# 04_-_COMMUNICATION.net
KiCad netlist of a schematic drawn in Altium Designer
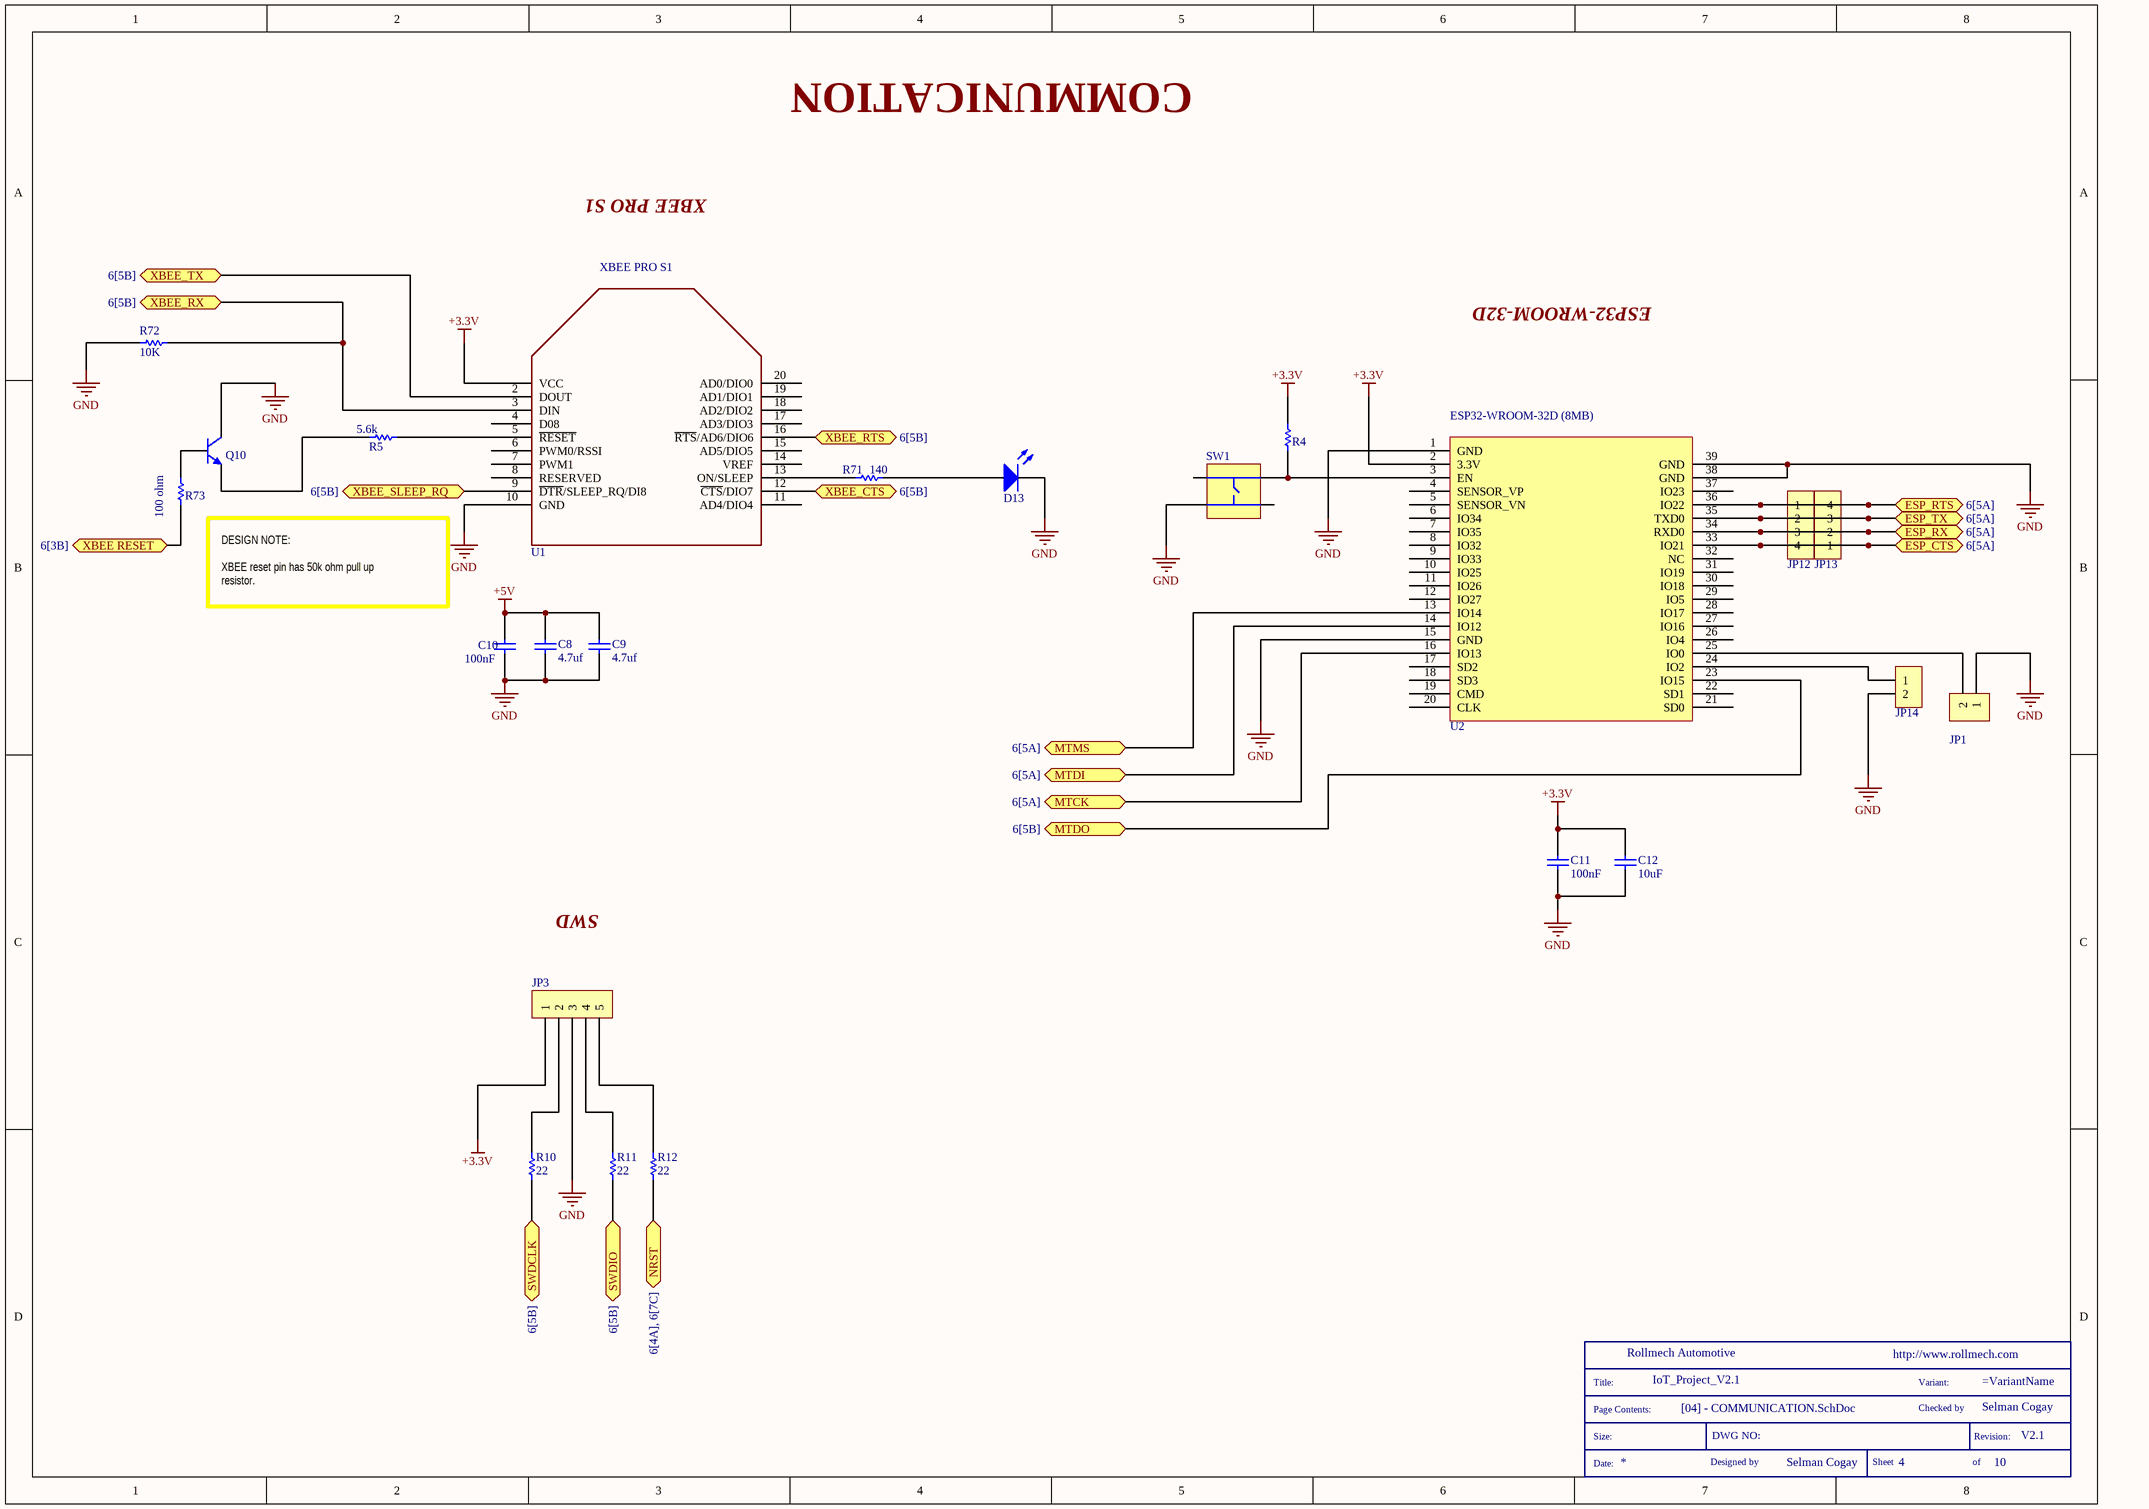
[diagram p0: [04] - COMMUNICATION.SchDoc]

(export (version "E")
  (design (tool "Eeschema 10.0.6"))
  (components
    (comp (ref "C8")
      (value "4.7uf")
      (footprint "CAP_CER_0603")
      (description "CAP CER 4.7PF 50V C0G 0603")
      (libsource (lib "Rollmech_Altium") (part "CGA3E2C0G1H4R7C080AA"))
    )
    (comp (ref "C9")
      (value "4.7uf")
      (footprint "CAP_CER_0603")
      (description "CAP CER 4.7PF 50V C0G 0603")
      (libsource (lib "Rollmech_Altium") (part "CGA3E2C0G1H4R7C080AA"))
    )
    (comp (ref "C10")
      (value "100nF")
      (footprint "CAP_CER_0603")
      (description "CAP CER 100nf 35V X5R 0603")
      (libsource (lib "Rollmech_Altium") (part "GMK107BJ104KAHT"))
    )
    (comp (ref "C11")
      (value "100nF")
      (footprint "CAP_CER_0603")
      (description "CAP CER 100nf 35V X5R 0603")
      (libsource (lib "Rollmech_Altium") (part "GMK107BJ104KAHT"))
    )
    (comp (ref "C12")
      (value "10uF")
      (footprint "CAP_CER_0805")
      (description "CAP CER 10UF 16V")
      (libsource (lib "Rollmech_Altium") (part "CGA4J1X5R1C106M125AC"))
    )
    (comp (ref "D13")
      (value "Blue Led")
      (footprint "RES_0603")
      (description "LED BLUE CLEAR 2SMD")
      (libsource (lib "Rollmech_Altium") (part "EAST16084BA8"))
    )
    (comp (ref "JP1")
      (value "HDR 1X2 2.54MM")
      (footprint "HDR_FEMALE_1X2_2.54MM")
      (description "HDR FEMALE 1X2 2.54MM")
      (libsource (lib "") (part "PPTC021LFBN-RC_1"))
    )
    (comp (ref "JP3")
      (value "HDR FEMALE 1X5 2.54MM")
      (footprint "HDR_FEMALE_1X5_2.54MM")
      (libsource (lib "Rollmech_Altium") (part "PPTC051LFBN-RC"))
    )
    (comp (ref "JP12")
      (value "HDR FEMALE 1X4 2.54MM")
      (footprint "HDR_FEMALE_1X4_2.54MM")
      (libsource (lib "") (part "PPTC041LFBN-RC_1"))
    )
    (comp (ref "JP13")
      (value "HDR FEMALE 1X4 2.54MM")
      (footprint "HDR_FEMALE_1X4_2.54MM")
      (libsource (lib "Rollmech_Altium") (part "PPTC041LFBN-RC"))
    )
    (comp (ref "JP14")
      (value "HDR 1X2 2.54MM")
      (footprint "HDR_FEMALE_1X2_2.54MM")
      (description "HDR FEMALE 1X2 2.54MM")
      (libsource (lib "Rollmech_Altium") (part "PPTC021LFBN-RC"))
    )
    (comp (ref "Q10")
      (value "NPN 0.6A")
      (footprint "SOT-23 (TO-236)")
      (description "TRANS NPN 40V 0.6A SMD SOT23-3")
      (libsource (lib "Rollmech_Altium") (part "MMBT2222A-7-F"))
    )
    (comp (ref "R4")
      (value "1K 1/8W")
      (footprint "RES_0805")
      (description "RES SMD 1K OHM")
      (libsource (lib "Rollmech_Altium") (part "ERJ-6ENF1001V"))
    )
    (comp (ref "R5")
      (value "5.6k")
      (footprint "RES_0805")
      (description "RES SMD 5.6K OHM 1% 1/8W 0805")
      (libsource (lib "Rollmech_Altium") (part "ERJ-6ENF5601V"))
    )
    (comp (ref "R10")
      (value "22")
      (footprint "RES_0805")
      (description "RES SMD 22 OHM 5% 1/8W 0805")
      (libsource (lib "Rollmech_Altium") (part "ERJ-6GEYJ220V"))
    )
    (comp (ref "R11")
      (value "22")
      (footprint "RES_0805")
      (description "RES SMD 22 OHM 5% 1/8W 0805")
      (libsource (lib "Rollmech_Altium") (part "ERJ-6GEYJ220V"))
    )
    (comp (ref "R12")
      (value "22")
      (footprint "RES_0805")
      (description "RES SMD 22 OHM 5% 1/8W 0805")
      (libsource (lib "Rollmech_Altium") (part "ERJ-6GEYJ220V"))
    )
    (comp (ref "R71")
      (value "140")
      (footprint "RES_0805")
      (description "RES SMD 140 OHM 1% 1/8W 0805")
      (libsource (lib "Rollmech_Altium") (part "ERJ-6ENF1400V"))
    )
    (comp (ref "R72")
      (value "10K")
      (footprint "RES_0805")
      (description "RES SMD 10K OHM 1% 1/8W 0805")
      (libsource (lib "Rollmech_Altium") (part "ERJ-6ENF1002V"))
    )
    (comp (ref "R73")
      (value "100 ohm")
      (footprint "RES_0805")
      (description "RES SMD 100 OHM")
      (libsource (lib "Rollmech_Altium") (part "ERJ-6ENF1000V"))
    )
    (comp (ref "SW1")
      (value "PTS 647 SK38 SMTR2 LFS")
      (footprint "4.5x4.5 Tactile switch")
      (description "SWITCH TACTILE 4.5 X 4.5")
      (libsource (lib "Rollmech_Altium") (part "PTS 647 SK38 SMTR2 LFS"))
    )
    (comp (ref "U1")
      (value "XBEE PRO S1")
      (footprint "XBEE PRO S1")
      (description "XBEE PRO SERIES1")
      (libsource (lib "Rollmech_Altium") (part "XBP24-DKSJ"))
    )
    (comp (ref "U2")
      (value "ESP32-WROOM-32D (8MB)")
      (footprint "ESP32-WROOM-32D")
      (description "ESP32 WIFI MODULE 64MBITS SPI FLASH")
      (libsource (lib "Rollmech_Altium") (part "ESP32-WROOM-32D (8MB)"))
    )
  )
  (nets
    (net (code "1") (name "+3.3V") (class "Default")
      (node (ref "C11") (pin "2") (pinfunction "2_2") (pintype "passive"))
      (node (ref "C12") (pin "2") (pinfunction "2_2") (pintype "passive"))
      (node (ref "JP3") (pin "1") (pinfunction "1_1") (pintype "passive"))
      (node (ref "R4") (pin "2") (pinfunction "2_2") (pintype "passive"))
      (node (ref "U1") (pin "1") (pinfunction "VCC_1") (pintype "passive"))
      (node (ref "U2") (pin "2") (pinfunction "3.3V_2") (pintype "passive"))
    )
    (net (code "2") (name "+5V") (class "Default")
      (node (ref "C10") (pin "2") (pinfunction "2_2") (pintype "passive"))
      (node (ref "C8") (pin "2") (pinfunction "2_2") (pintype "passive"))
      (node (ref "C9") (pin "2") (pinfunction "2_2") (pintype "passive"))
    )
    (net (code "3") (name "/ESP_CTS") (class "Default")
      (node (ref "JP12") (pin "4") (pinfunction "4_4") (pintype "passive"))
      (node (ref "JP13") (pin "1") (pinfunction "1_1") (pintype "passive"))
      (node (ref "U2") (pin "33") (pinfunction "IO21_33") (pintype "passive"))
    )
    (net (code "4") (name "/ESP_RTS") (class "Default")
      (node (ref "JP12") (pin "1") (pinfunction "1_1") (pintype "passive"))
      (node (ref "JP13") (pin "4") (pinfunction "4_4") (pintype "passive"))
      (node (ref "U2") (pin "36") (pinfunction "IO22_36") (pintype "passive"))
    )
    (net (code "5") (name "/ESP_RX") (class "Default")
      (node (ref "JP12") (pin "3") (pinfunction "3_3") (pintype "passive"))
      (node (ref "JP13") (pin "2") (pinfunction "2_2") (pintype "passive"))
      (node (ref "U2") (pin "34") (pinfunction "RXD0_34") (pintype "passive"))
    )
    (net (code "6") (name "/ESP_TX") (class "Default")
      (node (ref "JP12") (pin "2") (pinfunction "2_2") (pintype "passive"))
      (node (ref "JP13") (pin "3") (pinfunction "3_3") (pintype "passive"))
      (node (ref "U2") (pin "35") (pinfunction "TXD0_35") (pintype "passive"))
    )
    (net (code "7") (name "/MTCK") (class "Default")
      (node (ref "U2") (pin "16") (pinfunction "IO13_16") (pintype "passive"))
    )
    (net (code "8") (name "/MTDI") (class "Default")
      (node (ref "U2") (pin "14") (pinfunction "IO12_14") (pintype "passive"))
    )
    (net (code "9") (name "/MTDO") (class "Default")
      (node (ref "U2") (pin "23") (pinfunction "IO15_23") (pintype "passive"))
    )
    (net (code "10") (name "/MTMS") (class "Default")
      (node (ref "U2") (pin "13") (pinfunction "IO14_13") (pintype "passive"))
    )
    (net (code "11") (name "/NRST") (class "Default")
      (node (ref "R12") (pin "1") (pinfunction "1_1") (pintype "passive"))
    )
    (net (code "12") (name "/SWDCLK") (class "Default")
      (node (ref "R10") (pin "1") (pinfunction "1_1") (pintype "passive"))
    )
    (net (code "13") (name "/SWDIO") (class "Default")
      (node (ref "R11") (pin "1") (pinfunction "1_1") (pintype "passive"))
    )
    (net (code "14") (name "/XBEE RESET") (class "Default")
      (node (ref "R73") (pin "1") (pinfunction "1_1") (pintype "passive"))
    )
    (net (code "15") (name "/XBEE_CTS") (class "Default")
      (node (ref "U1") (pin "12") (pinfunction "~{CTS}/DIO7_12") (pintype "passive"))
    )
    (net (code "16") (name "/XBEE_RTS") (class "Default")
      (node (ref "U1") (pin "16") (pinfunction "~{RTS}/AD6/DIO6_16") (pintype "passive"))
    )
    (net (code "17") (name "/XBEE_RX") (class "Default")
      (node (ref "R72") (pin "2") (pinfunction "2_2") (pintype "passive"))
      (node (ref "U1") (pin "3") (pinfunction "DIN_3") (pintype "passive"))
    )
    (net (code "18") (name "/XBEE_SLEEP_RQ") (class "Default")
      (node (ref "U1") (pin "9") (pinfunction "~{DTR}/SLEEP_RQ/DI8_9") (pintype "passive"))
    )
    (net (code "19") (name "/XBEE_TX") (class "Default")
      (node (ref "U1") (pin "2") (pinfunction "DOUT_2") (pintype "passive"))
    )
    (net (code "20") (name "GND") (class "Default")
      (node (ref "C10") (pin "1") (pinfunction "1_1") (pintype "passive"))
      (node (ref "C11") (pin "1") (pinfunction "1_1") (pintype "passive"))
      (node (ref "C12") (pin "1") (pinfunction "1_1") (pintype "passive"))
      (node (ref "C8") (pin "1") (pinfunction "1_1") (pintype "passive"))
      (node (ref "C9") (pin "1") (pinfunction "1_1") (pintype "passive"))
      (node (ref "D13") (pin "2") (pinfunction "K_2") (pintype "passive"))
      (node (ref "JP1") (pin "1") (pinfunction "1_1") (pintype "passive"))
      (node (ref "JP14") (pin "2") (pinfunction "2_2") (pintype "passive"))
      (node (ref "JP3") (pin "3") (pinfunction "3_3") (pintype "passive"))
      (node (ref "Q10") (pin "1") (pinfunction "C_1") (pintype "passive"))
      (node (ref "R72") (pin "1") (pinfunction "1_1") (pintype "passive"))
      (node (ref "SW1") (pin "3") (pinfunction "3_3") (pintype "passive"))
      (node (ref "U1") (pin "10") (pinfunction "GND_10") (pintype "passive"))
      (node (ref "U2") (pin "1") (pinfunction "GND_1") (pintype "passive"))
      (node (ref "U2") (pin "15") (pinfunction "GND_15") (pintype "passive"))
      (node (ref "U2") (pin "38") (pinfunction "GND_38") (pintype "passive"))
      (node (ref "U2") (pin "39") (pinfunction "GND_39") (pintype "passive"))
    )
    (net (code "21") (name "Net-(D13-A)") (class "Default")
      (node (ref "D13") (pin "1") (pinfunction "A_1") (pintype "passive"))
      (node (ref "R71") (pin "2") (pinfunction "2_2") (pintype "passive"))
    )
    (net (code "22") (name "Net-(JP3-Pad2)") (class "Default")
      (node (ref "JP3") (pin "2") (pinfunction "2_2") (pintype "passive"))
      (node (ref "R10") (pin "2") (pinfunction "2_2") (pintype "passive"))
    )
    (net (code "23") (name "Net-(JP3-Pad4)") (class "Default")
      (node (ref "JP3") (pin "4") (pinfunction "4_4") (pintype "passive"))
      (node (ref "R11") (pin "2") (pinfunction "2_2") (pintype "passive"))
    )
    (net (code "24") (name "Net-(JP3-Pad5)") (class "Default")
      (node (ref "JP3") (pin "5") (pinfunction "5_5") (pintype "passive"))
      (node (ref "R12") (pin "2") (pinfunction "2_2") (pintype "passive"))
    )
    (net (code "25") (name "Net-(Q10-B)") (class "Default")
      (node (ref "Q10") (pin "2") (pinfunction "B_2") (pintype "passive"))
      (node (ref "R73") (pin "2") (pinfunction "2_2") (pintype "passive"))
    )
    (net (code "26") (name "Net-(Q10-E)") (class "Default")
      (node (ref "Q10") (pin "3") (pinfunction "E_3") (pintype "passive"))
      (node (ref "R5") (pin "2") (pinfunction "2_2") (pintype "passive"))
    )
    (net (code "27") (name "Net-(U1-ON{slash}SLEEP)") (class "Default")
      (node (ref "R71") (pin "1") (pinfunction "1_1") (pintype "passive"))
      (node (ref "U1") (pin "13") (pinfunction "ON/SLEEP_13") (pintype "passive"))
    )
    (net (code "28") (name "Net-(U1-~{RESET})") (class "Default")
      (node (ref "R5") (pin "1") (pinfunction "1_1") (pintype "passive"))
      (node (ref "U1") (pin "5") (pinfunction "~{RESET}_5") (pintype "passive"))
    )
    (net (code "29") (name "Net-(U2-EN)") (class "Default")
      (node (ref "R4") (pin "1") (pinfunction "1_1") (pintype "passive"))
      (node (ref "SW1") (pin "2") (pinfunction "2_2") (pintype "passive"))
      (node (ref "U2") (pin "3") (pinfunction "EN_3") (pintype "passive"))
    )
    (net (code "30") (name "Net-(U2-IO0)") (class "Default")
      (node (ref "JP1") (pin "2") (pinfunction "2_2") (pintype "passive"))
      (node (ref "U2") (pin "25") (pinfunction "IO0_25") (pintype "passive"))
    )
    (net (code "31") (name "Net-(U2-IO2)") (class "Default")
      (node (ref "JP14") (pin "1") (pinfunction "1_1") (pintype "passive"))
      (node (ref "U2") (pin "24") (pinfunction "IO2_24") (pintype "passive"))
    )
    (net (code "32") (name "unconnected-(SW1-Pad1)") (class "Default")
      (node (ref "SW1") (pin "1") (pinfunction "1_1") (pintype "passive"))
    )
    (net (code "33") (name "unconnected-(SW1-Pad4)") (class "Default")
      (node (ref "SW1") (pin "4") (pinfunction "4_4") (pintype "passive"))
    )
    (net (code "34") (name "unconnected-(U1-AD0{slash}DIO0-Pad20)") (class "Default")
      (node (ref "U1") (pin "20") (pinfunction "AD0/DIO0_20") (pintype "passive"))
    )
    (net (code "35") (name "unconnected-(U1-AD1{slash}DIO1-Pad19)") (class "Default")
      (node (ref "U1") (pin "19") (pinfunction "AD1/DIO1_19") (pintype "passive"))
    )
    (net (code "36") (name "unconnected-(U1-AD2{slash}DIO2-Pad18)") (class "Default")
      (node (ref "U1") (pin "18") (pinfunction "AD2/DIO2_18") (pintype "passive"))
    )
    (net (code "37") (name "unconnected-(U1-AD3{slash}DIO3-Pad17)") (class "Default")
      (node (ref "U1") (pin "17") (pinfunction "AD3/DIO3_17") (pintype "passive"))
    )
    (net (code "38") (name "unconnected-(U1-AD4{slash}DIO4-Pad11)") (class "Default")
      (node (ref "U1") (pin "11") (pinfunction "AD4/DIO4_11") (pintype "passive"))
    )
    (net (code "39") (name "unconnected-(U1-AD5{slash}DIO5-Pad15)") (class "Default")
      (node (ref "U1") (pin "15") (pinfunction "AD5/DIO5_15") (pintype "passive"))
    )
    (net (code "40") (name "unconnected-(U1-D08-Pad4)") (class "Default")
      (node (ref "U1") (pin "4") (pinfunction "D08_4") (pintype "passive"))
    )
    (net (code "41") (name "unconnected-(U1-PWM0{slash}RSSI-Pad6)") (class "Default")
      (node (ref "U1") (pin "6") (pinfunction "PWM0/RSSI_6") (pintype "passive"))
    )
    (net (code "42") (name "unconnected-(U1-PWM1-Pad7)") (class "Default")
      (node (ref "U1") (pin "7") (pinfunction "PWM1_7") (pintype "passive"))
    )
    (net (code "43") (name "unconnected-(U1-RESERVED-Pad8)") (class "Default")
      (node (ref "U1") (pin "8") (pinfunction "RESERVED_8") (pintype "passive"))
    )
    (net (code "44") (name "unconnected-(U1-VREF-Pad14)") (class "Default")
      (node (ref "U1") (pin "14") (pinfunction "VREF_14") (pintype "passive"))
    )
    (net (code "45") (name "unconnected-(U2-CLK-Pad20)") (class "Default")
      (node (ref "U2") (pin "20") (pinfunction "CLK_20") (pintype "passive"))
    )
    (net (code "46") (name "unconnected-(U2-CMD-Pad19)") (class "Default")
      (node (ref "U2") (pin "19") (pinfunction "CMD_19") (pintype "passive"))
    )
    (net (code "47") (name "unconnected-(U2-IO4-Pad26)") (class "Default")
      (node (ref "U2") (pin "26") (pinfunction "IO4_26") (pintype "passive"))
    )
    (net (code "48") (name "unconnected-(U2-IO5-Pad29)") (class "Default")
      (node (ref "U2") (pin "29") (pinfunction "IO5_29") (pintype "passive"))
    )
    (net (code "49") (name "unconnected-(U2-IO16-Pad27)") (class "Default")
      (node (ref "U2") (pin "27") (pinfunction "IO16_27") (pintype "passive"))
    )
    (net (code "50") (name "unconnected-(U2-IO17-Pad28)") (class "Default")
      (node (ref "U2") (pin "28") (pinfunction "IO17_28") (pintype "passive"))
    )
    (net (code "51") (name "unconnected-(U2-IO18-Pad30)") (class "Default")
      (node (ref "U2") (pin "30") (pinfunction "IO18_30") (pintype "passive"))
    )
    (net (code "52") (name "unconnected-(U2-IO19-Pad31)") (class "Default")
      (node (ref "U2") (pin "31") (pinfunction "IO19_31") (pintype "passive"))
    )
    (net (code "53") (name "unconnected-(U2-IO23-Pad37)") (class "Default")
      (node (ref "U2") (pin "37") (pinfunction "IO23_37") (pintype "passive"))
    )
    (net (code "54") (name "unconnected-(U2-IO25-Pad10)") (class "Default")
      (node (ref "U2") (pin "10") (pinfunction "IO25_10") (pintype "passive"))
    )
    (net (code "55") (name "unconnected-(U2-IO26-Pad11)") (class "Default")
      (node (ref "U2") (pin "11") (pinfunction "IO26_11") (pintype "passive"))
    )
    (net (code "56") (name "unconnected-(U2-IO27-Pad12)") (class "Default")
      (node (ref "U2") (pin "12") (pinfunction "IO27_12") (pintype "passive"))
    )
    (net (code "57") (name "unconnected-(U2-IO32-Pad8)") (class "Default")
      (node (ref "U2") (pin "8") (pinfunction "IO32_8") (pintype "passive"))
    )
    (net (code "58") (name "unconnected-(U2-IO33-Pad9)") (class "Default")
      (node (ref "U2") (pin "9") (pinfunction "IO33_9") (pintype "passive"))
    )
    (net (code "59") (name "unconnected-(U2-IO34-Pad6)") (class "Default")
      (node (ref "U2") (pin "6") (pinfunction "IO34_6") (pintype "passive"))
    )
    (net (code "60") (name "unconnected-(U2-IO35-Pad7)") (class "Default")
      (node (ref "U2") (pin "7") (pinfunction "IO35_7") (pintype "passive"))
    )
    (net (code "61") (name "unconnected-(U2-NC-Pad32)") (class "Default")
      (node (ref "U2") (pin "32") (pinfunction "NC_32") (pintype "passive"))
    )
    (net (code "62") (name "unconnected-(U2-SD0-Pad21)") (class "Default")
      (node (ref "U2") (pin "21") (pinfunction "SD0_21") (pintype "passive"))
    )
    (net (code "63") (name "unconnected-(U2-SD1-Pad22)") (class "Default")
      (node (ref "U2") (pin "22") (pinfunction "SD1_22") (pintype "passive"))
    )
    (net (code "64") (name "unconnected-(U2-SD2-Pad17)") (class "Default")
      (node (ref "U2") (pin "17") (pinfunction "SD2_17") (pintype "passive"))
    )
    (net (code "65") (name "unconnected-(U2-SD3-Pad18)") (class "Default")
      (node (ref "U2") (pin "18") (pinfunction "SD3_18") (pintype "passive"))
    )
    (net (code "66") (name "unconnected-(U2-SENSOR_VN-Pad5)") (class "Default")
      (node (ref "U2") (pin "5") (pinfunction "SENSOR_VN_5") (pintype "passive"))
    )
    (net (code "67") (name "unconnected-(U2-SENSOR_VP-Pad4)") (class "Default")
      (node (ref "U2") (pin "4") (pinfunction "SENSOR_VP_4") (pintype "passive"))
    )
  )
)
